# MCU.net
KiCad netlist of a schematic drawn in Altium Designer
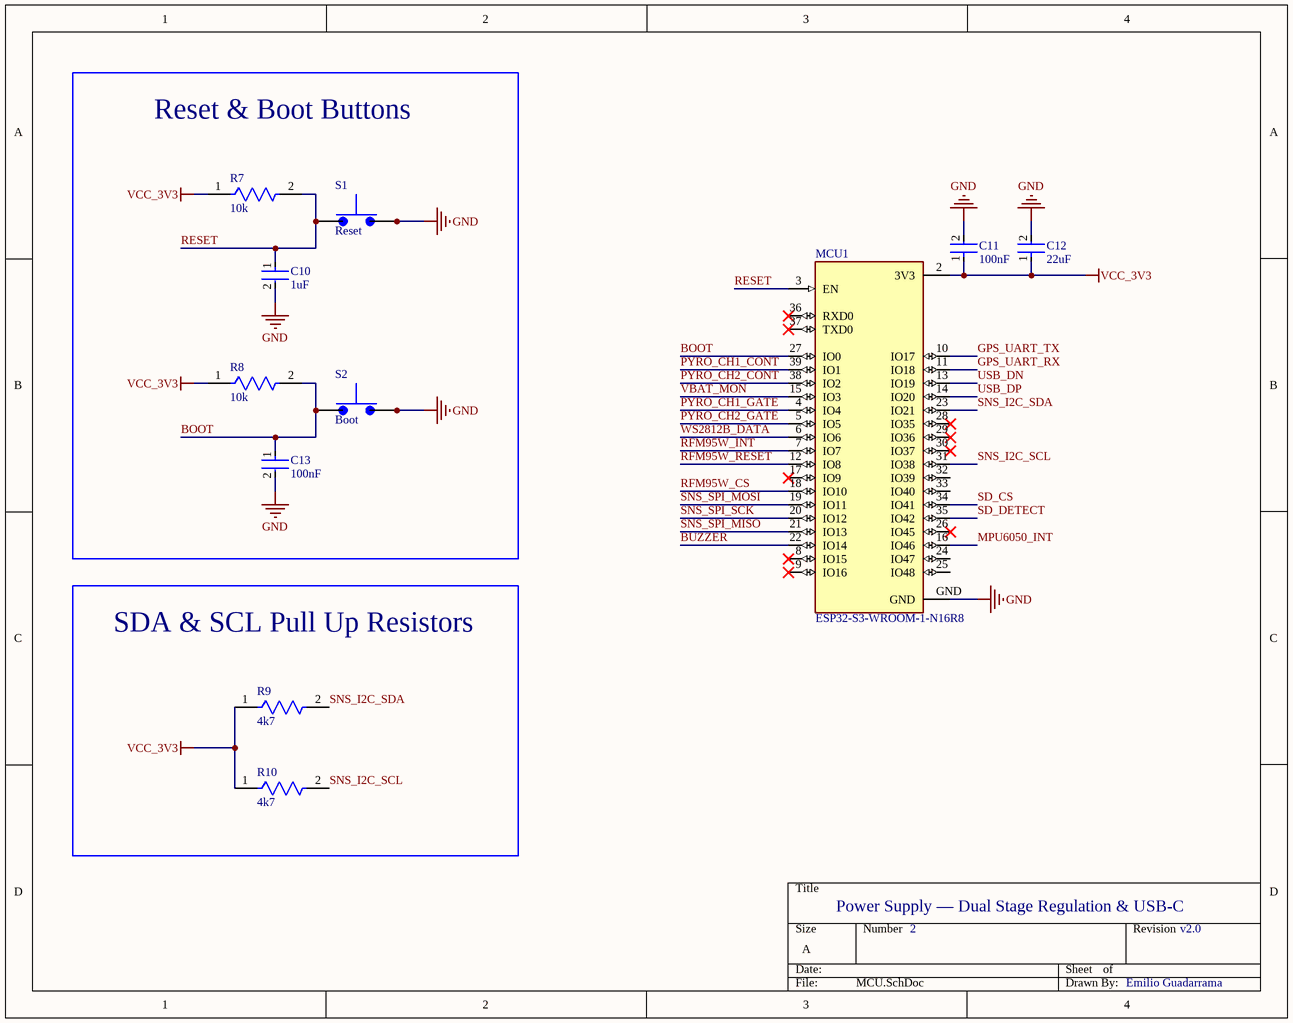
[diagram p0: MCU.SchDoc]

(export (version "E")
  (design (tool "Eeschema 10.0.6"))
  (components
    (comp (ref "C10")
      (value "1uF")
      (footprint "FP-C0805C-DN-MFG")
      (description "CAP CER 0.1UF 50V X7R 0805")
      (fields
        (field (name "MANUFACTURER PART NUMBER") "C0805C104K5RACTU")
        (field (name "MANUFACTURER") "KEMET")
      )
      (libsource (lib "Altium Content Vault") (part "b4654b650e69147ec39a6b967a45e02"))
    )
    (comp (ref "C11")
      (value "100nF")
      (footprint "FP-C0805C-DN-MFG")
      (description "CAP CER 0.1UF 50V X7R 0805")
      (fields
        (field (name "MANUFACTURER PART NUMBER") "C0805C104K5RACTU")
        (field (name "MANUFACTURER") "KEMET")
      )
      (libsource (lib "Altium Content Vault") (part "b4654b650e69147ec39a6b967a45e02"))
    )
    (comp (ref "C12")
      (value "22uF")
      (footprint "FP-C0805C-DN-MFG")
      (description "CAP CER 0.1UF 50V X7R 0805")
      (fields
        (field (name "MANUFACTURER PART NUMBER") "C0805C104K5RACTU")
        (field (name "MANUFACTURER") "KEMET")
      )
      (libsource (lib "Altium Content Vault") (part "b4654b650e69147ec39a6b967a45e02"))
    )
    (comp (ref "C13")
      (value "100nF")
      (footprint "FP-C0805C-DN-MFG")
      (description "CAP CER 0.1UF 50V X7R 0805")
      (fields
        (field (name "MANUFACTURER PART NUMBER") "C0805C104K5RACTU")
        (field (name "MANUFACTURER") "KEMET")
      )
      (libsource (lib "Altium Content Vault") (part "b4654b650e69147ec39a6b967a45e02"))
    )
    (comp (ref "MCU1")
      (value "ESP32-S3-WROOM-1-N16R8")
      (footprint "XCVR_ESP32-S3-WROOM-1-N16R2")
      (description "Bluetooth, WiFi 802.11b/g/n, Bluetooth v5.0 Transceiver Module 2.4GHz PCB Trace Surface Mount")
      (fields (field (name "MF") "Espressif Systems") (field (name "MP") "ESP32S3WROOM1N16R2"))
      (libsource (lib "ESP32-S3-WROOM-1-N16R2") (part "ESP32-S3-WROOM-1-N16R2"))
    )
    (comp (ref "R7")
      (value "10k")
      (footprint "FP-MCT0603-IPC_A")
      (description "RES SMD 100 OHM 1% 1/8W 0603")
      (fields (field (name "TOLERANCE") "0.1%"))
      (libsource (lib "Altium Content Vault") (part "1029c3af85768c4190bb7ad29bc67b5"))
    )
    (comp (ref "R8")
      (value "10k")
      (footprint "FP-MCT0603-IPC_A")
      (description "RES SMD 100 OHM 1% 1/8W 0603")
      (fields (field (name "TOLERANCE") "0.1%"))
      (libsource (lib "Altium Content Vault") (part "1029c3af85768c4190bb7ad29bc67b5"))
    )
    (comp (ref "R9")
      (value "4k7")
      (footprint "FP-MCT0603-IPC_A")
      (description "RES SMD 100 OHM 1% 1/8W 0603")
      (fields (field (name "TOLERANCE") "0.1%"))
      (libsource (lib "Altium Content Vault") (part "1029c3af85768c4190bb7ad29bc67b5"))
    )
    (comp (ref "R10")
      (value "4k7")
      (footprint "FP-MCT0603-IPC_A")
      (description "RES SMD 100 OHM 1% 1/8W 0603")
      (fields (field (name "TOLERANCE") "0.1%"))
      (libsource (lib "Altium Content Vault") (part "1029c3af85768c4190bb7ad29bc67b5"))
    )
    (comp (ref "S1")
      (value "Reset")
      (footprint "SW_SKRPABE010")
      (description "Switch Tactile N.O. SPST Button J-Bend 0.05A 16VDC 1.57N SMD Automotive T/R")
      (fields (field (name "MF") "ALPS") (field (name "MP") "SKRPABE010"))
      (libsource (lib "Button-SKRPABE010") (part "SKRPABE010"))
    )
    (comp (ref "S2")
      (value "Boot")
      (footprint "SW_SKRPABE010")
      (description "Switch Tactile N.O. SPST Button J-Bend 0.05A 16VDC 1.57N SMD Automotive T/R")
      (fields (field (name "MF") "ALPS") (field (name "MP") "SKRPABE010"))
      (libsource (lib "Button-SKRPABE010") (part "SKRPABE010"))
    )
  )
  (nets
    (net (code "1") (name "/BOOT") (class "Default")
      (node (ref "C13") (pin "1") (pinfunction "1_1") (pintype "passive"))
      (node (ref "MCU1") (pin "27") (pinfunction "IO0_27") (pintype "bidirectional"))
      (node (ref "R8") (pin "2") (pinfunction "2_2") (pintype "passive"))
      (node (ref "S2") (pin "1") (pinfunction "1_1") (pintype "passive"))
      (node (ref "S2") (pin "2") (pinfunction "1_2") (pintype "passive"))
    )
    (net (code "2") (name "/BUZZER") (class "Default")
      (node (ref "MCU1") (pin "22") (pinfunction "IO14_22") (pintype "bidirectional"))
    )
    (net (code "3") (name "/GPS_UART_RX") (class "Default")
      (node (ref "MCU1") (pin "11") (pinfunction "IO18_11") (pintype "bidirectional"))
    )
    (net (code "4") (name "/GPS_UART_TX") (class "Default")
      (node (ref "MCU1") (pin "10") (pinfunction "IO17_10") (pintype "bidirectional"))
    )
    (net (code "5") (name "/MPU6050_INT") (class "Default")
      (node (ref "MCU1") (pin "16") (pinfunction "IO46_16") (pintype "bidirectional"))
    )
    (net (code "6") (name "/PYRO_CH1_CONT") (class "Default")
      (node (ref "MCU1") (pin "39") (pinfunction "IO1_39") (pintype "bidirectional"))
    )
    (net (code "7") (name "/PYRO_CH1_GATE") (class "Default")
      (node (ref "MCU1") (pin "4") (pinfunction "IO4_4") (pintype "bidirectional"))
    )
    (net (code "8") (name "/PYRO_CH2_CONT") (class "Default")
      (node (ref "MCU1") (pin "38") (pinfunction "IO2_38") (pintype "bidirectional"))
    )
    (net (code "9") (name "/PYRO_CH2_GATE") (class "Default")
      (node (ref "MCU1") (pin "5") (pinfunction "IO5_5") (pintype "bidirectional"))
    )
    (net (code "10") (name "/RESET") (class "Default")
      (node (ref "C10") (pin "1") (pinfunction "1_1") (pintype "passive"))
      (node (ref "MCU1") (pin "3") (pinfunction "EN_3") (pintype "input"))
      (node (ref "R7") (pin "2") (pinfunction "2_2") (pintype "passive"))
      (node (ref "S1") (pin "1") (pinfunction "1_1") (pintype "passive"))
      (node (ref "S1") (pin "2") (pinfunction "1_2") (pintype "passive"))
    )
    (net (code "11") (name "/RFM95W_CS") (class "Default")
      (node (ref "MCU1") (pin "18") (pinfunction "IO10_18") (pintype "bidirectional"))
    )
    (net (code "12") (name "/RFM95W_INT") (class "Default")
      (node (ref "MCU1") (pin "7") (pinfunction "IO7_7") (pintype "bidirectional"))
    )
    (net (code "13") (name "/RFM95W_RESET") (class "Default")
      (node (ref "MCU1") (pin "12") (pinfunction "IO8_12") (pintype "bidirectional"))
    )
    (net (code "14") (name "/SD_CS") (class "Default")
      (node (ref "MCU1") (pin "34") (pinfunction "IO41_34") (pintype "bidirectional"))
    )
    (net (code "15") (name "/SD_DETECT") (class "Default")
      (node (ref "MCU1") (pin "35") (pinfunction "IO42_35") (pintype "bidirectional"))
    )
    (net (code "16") (name "/SNS_I2C_SCL") (class "Default")
      (node (ref "MCU1") (pin "31") (pinfunction "IO38_31") (pintype "bidirectional"))
      (node (ref "R10") (pin "2") (pinfunction "2_2") (pintype "passive"))
    )
    (net (code "17") (name "/SNS_I2C_SDA") (class "Default")
      (node (ref "MCU1") (pin "23") (pinfunction "IO21_23") (pintype "bidirectional"))
      (node (ref "R9") (pin "2") (pinfunction "2_2") (pintype "passive"))
    )
    (net (code "18") (name "/SNS_SPI_MISO") (class "Default")
      (node (ref "MCU1") (pin "21") (pinfunction "IO13_21") (pintype "bidirectional"))
    )
    (net (code "19") (name "/SNS_SPI_MOSI") (class "Default")
      (node (ref "MCU1") (pin "19") (pinfunction "IO11_19") (pintype "bidirectional"))
    )
    (net (code "20") (name "/SNS_SPI_SCK") (class "Default")
      (node (ref "MCU1") (pin "20") (pinfunction "IO12_20") (pintype "bidirectional"))
    )
    (net (code "21") (name "/USB_DN") (class "Default")
      (node (ref "MCU1") (pin "13") (pinfunction "IO19_13") (pintype "bidirectional"))
    )
    (net (code "22") (name "/USB_DP") (class "Default")
      (node (ref "MCU1") (pin "14") (pinfunction "IO20_14") (pintype "bidirectional"))
    )
    (net (code "23") (name "/VBAT_MON") (class "Default")
      (node (ref "MCU1") (pin "15") (pinfunction "IO3_15") (pintype "bidirectional"))
    )
    (net (code "24") (name "/WS2812B_DATA") (class "Default")
      (node (ref "MCU1") (pin "6") (pinfunction "IO6_6") (pintype "bidirectional"))
    )
    (net (code "25") (name "GND") (class "Default")
      (node (ref "C10") (pin "2") (pinfunction "2_2") (pintype "passive"))
      (node (ref "C11") (pin "2") (pinfunction "2_2") (pintype "passive"))
      (node (ref "C12") (pin "2") (pinfunction "2_2") (pintype "passive"))
      (node (ref "C13") (pin "2") (pinfunction "2_2") (pintype "passive"))
      (node (ref "MCU1") (pin "GND") (pinfunction "GND_GND") (pintype "power_in"))
      (node (ref "S1") (pin "3") (pinfunction "2_3") (pintype "passive"))
      (node (ref "S1") (pin "4") (pinfunction "2_4") (pintype "passive"))
      (node (ref "S2") (pin "3") (pinfunction "2_3") (pintype "passive"))
      (node (ref "S2") (pin "4") (pinfunction "2_4") (pintype "passive"))
    )
    (net (code "26") (name "VCC_3V3") (class "Default")
      (node (ref "C11") (pin "1") (pinfunction "1_1") (pintype "passive"))
      (node (ref "C12") (pin "1") (pinfunction "1_1") (pintype "passive"))
      (node (ref "MCU1") (pin "2") (pinfunction "3V3_2") (pintype "power_in"))
      (node (ref "R10") (pin "1") (pinfunction "1_1") (pintype "passive"))
      (node (ref "R7") (pin "1") (pinfunction "1_1") (pintype "passive"))
      (node (ref "R8") (pin "1") (pinfunction "1_1") (pintype "passive"))
      (node (ref "R9") (pin "1") (pinfunction "1_1") (pintype "passive"))
    )
    (net (code "27") (name "unconnected-(MCU1-IO9-Pad17)") (class "Default")
      (node (ref "MCU1") (pin "17") (pinfunction "IO9_17") (pintype "bidirectional+no_connect"))
    )
    (net (code "28") (name "unconnected-(MCU1-IO15-Pad8)") (class "Default")
      (node (ref "MCU1") (pin "8") (pinfunction "IO15_8") (pintype "bidirectional+no_connect"))
    )
    (net (code "29") (name "unconnected-(MCU1-IO16-Pad9)") (class "Default")
      (node (ref "MCU1") (pin "9") (pinfunction "IO16_9") (pintype "bidirectional+no_connect"))
    )
    (net (code "30") (name "unconnected-(MCU1-IO35-Pad28)") (class "Default")
      (node (ref "MCU1") (pin "28") (pinfunction "IO35_28") (pintype "bidirectional+no_connect"))
    )
    (net (code "31") (name "unconnected-(MCU1-IO36-Pad29)") (class "Default")
      (node (ref "MCU1") (pin "29") (pinfunction "IO36_29") (pintype "bidirectional+no_connect"))
    )
    (net (code "32") (name "unconnected-(MCU1-IO37-Pad30)") (class "Default")
      (node (ref "MCU1") (pin "30") (pinfunction "IO37_30") (pintype "bidirectional+no_connect"))
    )
    (net (code "33") (name "unconnected-(MCU1-IO39-Pad32)") (class "Default")
      (node (ref "MCU1") (pin "32") (pinfunction "IO39_32") (pintype "bidirectional"))
    )
    (net (code "34") (name "unconnected-(MCU1-IO40-Pad33)") (class "Default")
      (node (ref "MCU1") (pin "33") (pinfunction "IO40_33") (pintype "bidirectional"))
    )
    (net (code "35") (name "unconnected-(MCU1-IO45-Pad26)") (class "Default")
      (node (ref "MCU1") (pin "26") (pinfunction "IO45_26") (pintype "bidirectional+no_connect"))
    )
    (net (code "36") (name "unconnected-(MCU1-IO47-Pad24)") (class "Default")
      (node (ref "MCU1") (pin "24") (pinfunction "IO47_24") (pintype "bidirectional"))
    )
    (net (code "37") (name "unconnected-(MCU1-IO48-Pad25)") (class "Default")
      (node (ref "MCU1") (pin "25") (pinfunction "IO48_25") (pintype "bidirectional"))
    )
    (net (code "38") (name "unconnected-(MCU1-RXD0-Pad36)") (class "Default")
      (node (ref "MCU1") (pin "36") (pinfunction "RXD0_36") (pintype "bidirectional+no_connect"))
    )
    (net (code "39") (name "unconnected-(MCU1-TXD0-Pad37)") (class "Default")
      (node (ref "MCU1") (pin "37") (pinfunction "TXD0_37") (pintype "bidirectional+no_connect"))
    )
  )
)
